# H10R4.net
KiCad netlist of a schematic drawn in EAGLE
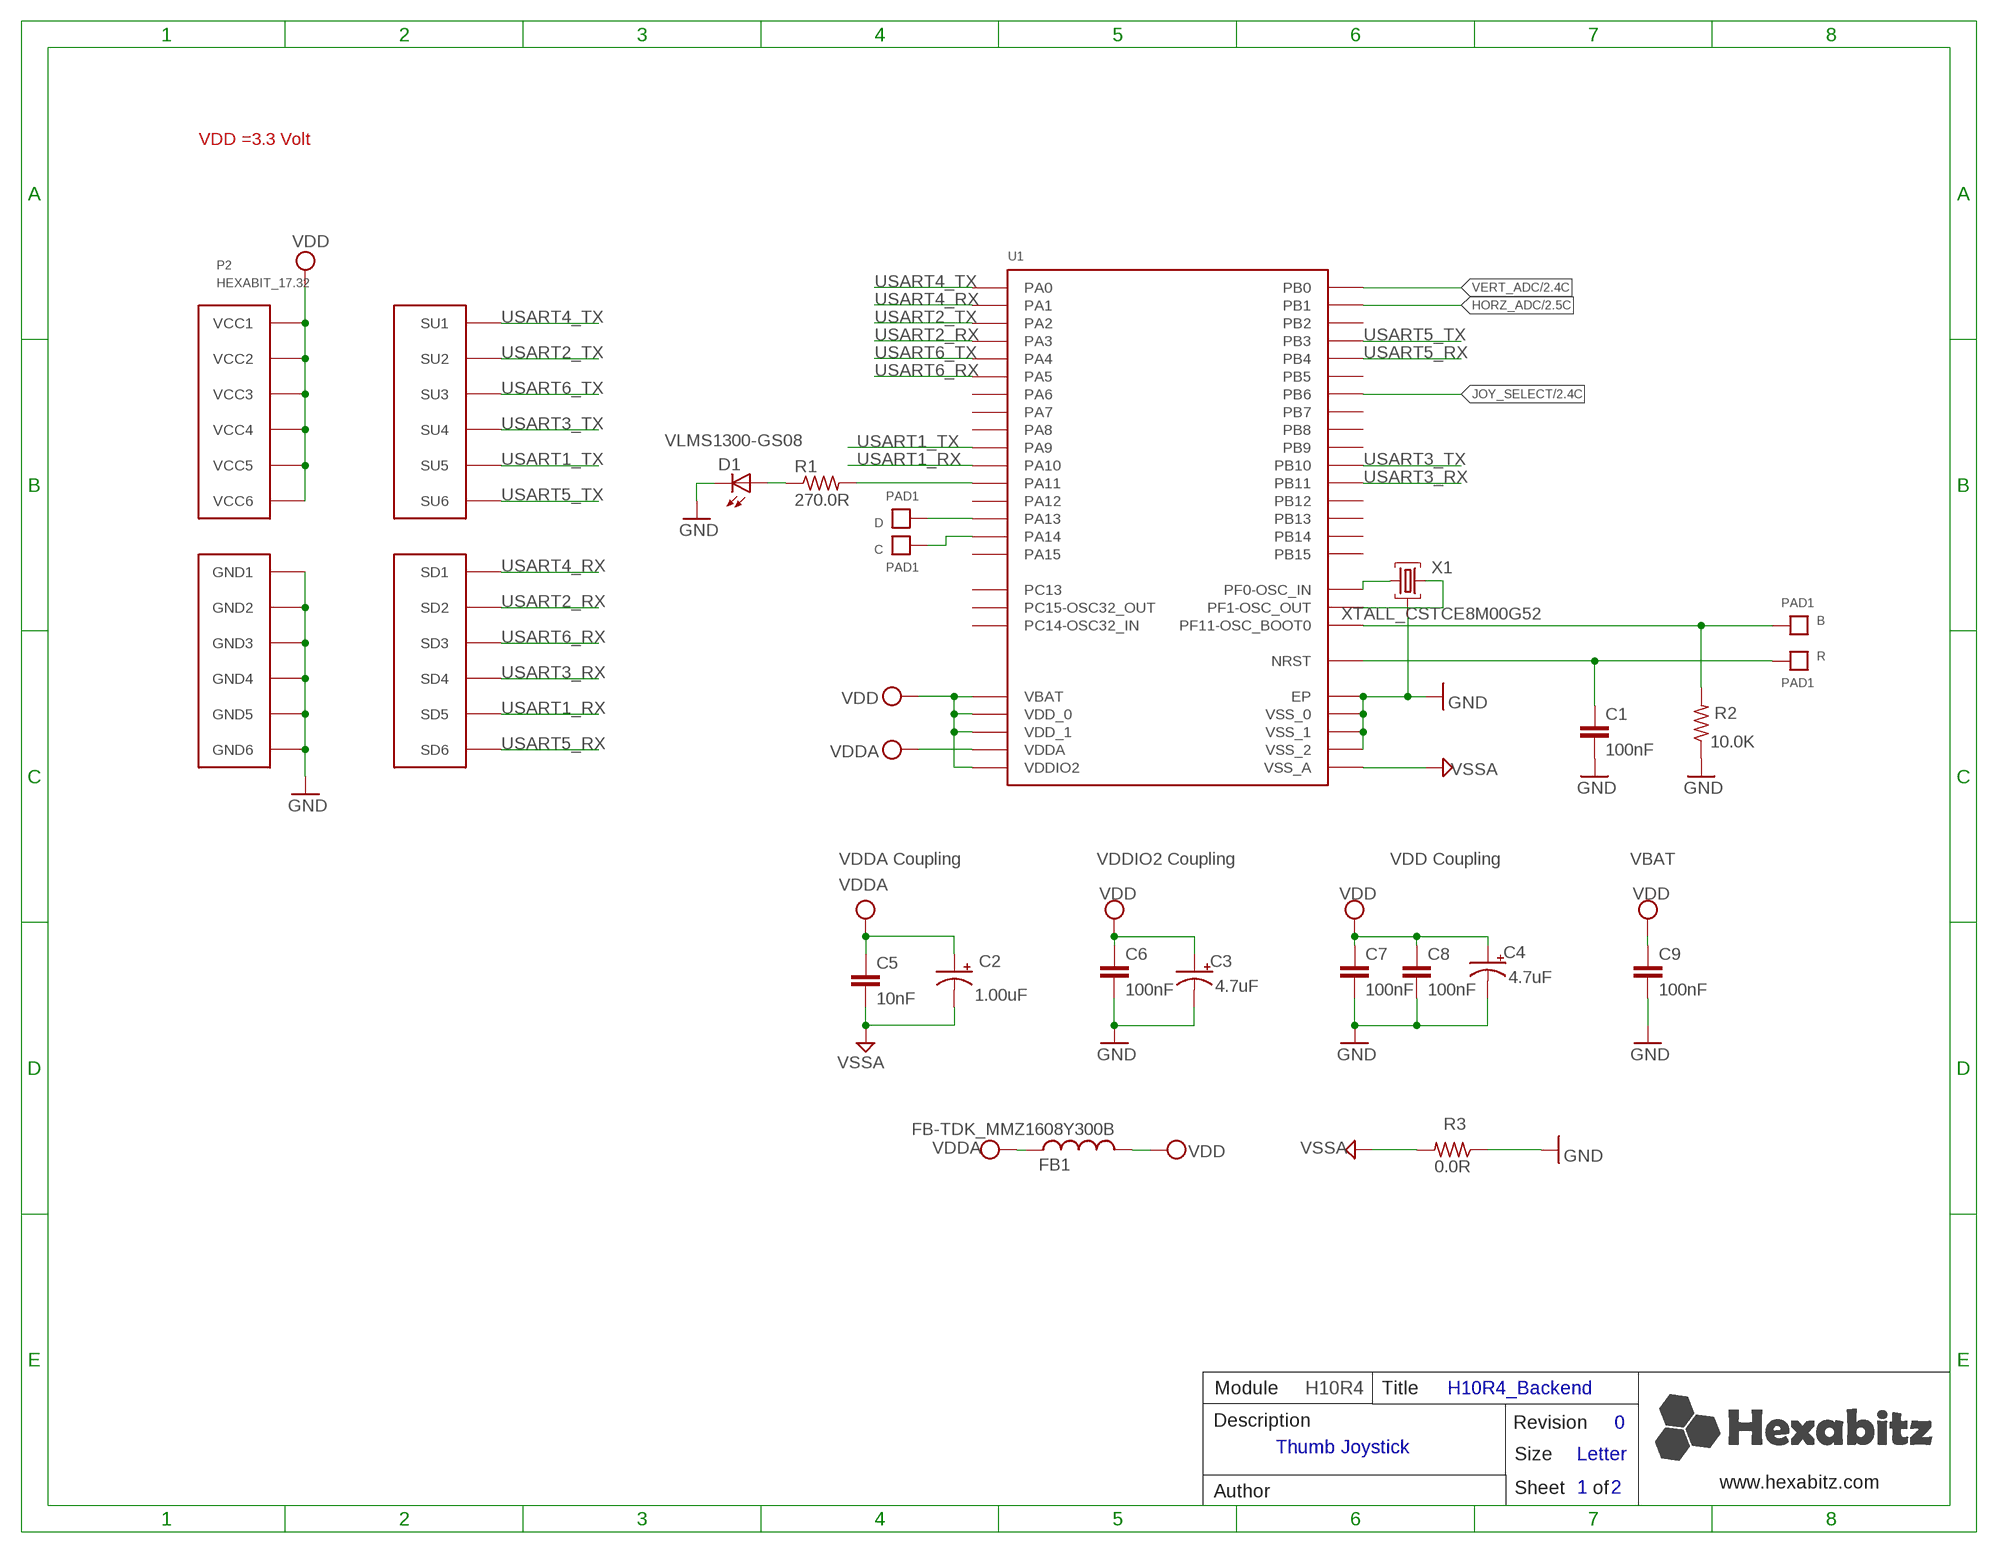
[diagram p0: schematic, sheet 1]
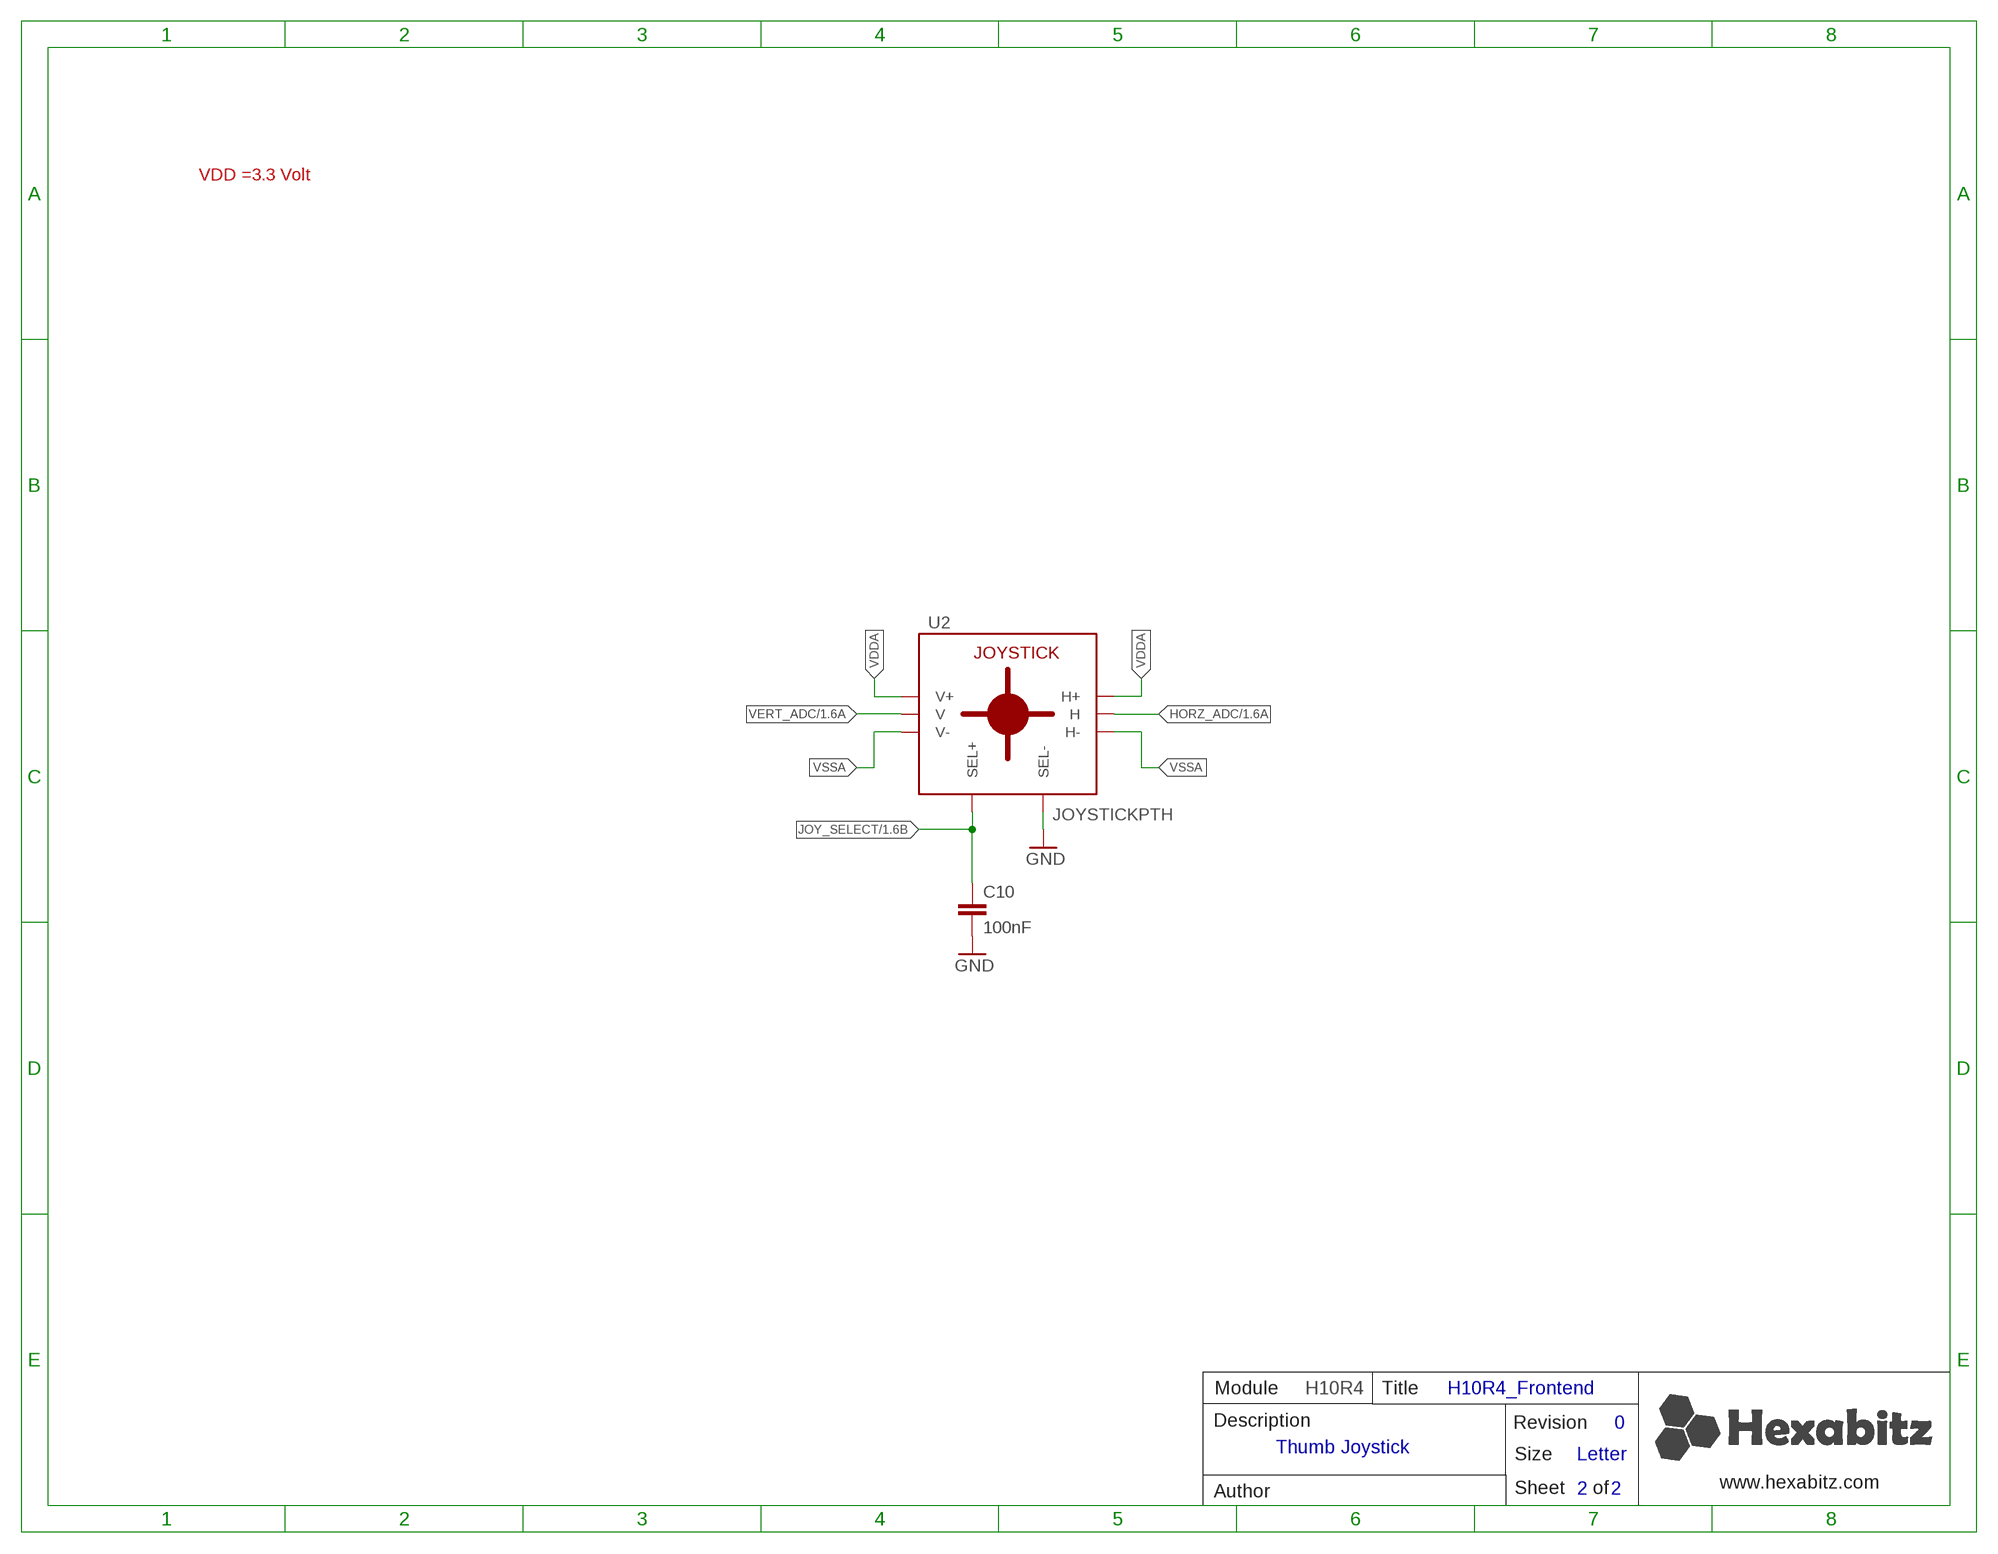
[diagram p1: schematic, sheet 2]

(export (version "E")
  (design (tool "Eeschema 10.0.6"))
  (components
    (comp (ref "B")
      (value "PAD1")
      (footprint "eagle-import:PAD1")
      (libsource (lib "eagle-import") (part "PAD1"))
    )
    (comp (ref "C")
      (value "PAD1")
      (footprint "eagle-import:PAD1")
      (libsource (lib "eagle-import") (part "PAD1"))
    )
    (comp (ref "C1")
      (value "100nF")
      (footprint "eagle-import:C-0603")
      (fields
        (field (name "CAPACITANCE") "100nF")
        (field (name "MFN") "KEMET")
        (field (name "MPN") "C0603C104K8RACTU")
        (field (name "OCTOPART_URL") "https://octopart.com/c0603c104k8ractu-kemet-145075?r=sp&s=9bS9ASSwSEqMCE9KBEQZ0g")
        (field (name "TOLERANCE") "10%")
        (field (name "VOLTAGE_RATING") "10V")
      )
      (libsource (lib "eagle-import") (part "C-0603"))
    )
    (comp (ref "C2")
      (value "1.00uF")
      (footprint "eagle-import:C-0805-POL")
      (fields
        (field (name "CAPACITANCE") "1.00uF")
        (field (name "MFN") "Yageo")
        (field (name "MPN") "CC0805KKX7R7BB105")
        (field (name "OCTOPART_URL") "https://octopart.com/cc0805kkx7r7bb105-yageo-8376555?r=sp&s=YKl1wwtkROau_X5nniH2ig")
        (field (name "TOLERANCE") "10%")
        (field (name "VOLTAGE_RATING") "16V")
      )
      (libsource (lib "eagle-import") (part "C-0805-POL"))
    )
    (comp (ref "C3")
      (value "4.7uF")
      (footprint "eagle-import:C-0805-POL")
      (fields
        (field (name "CAPACITANCE") "4.7uF")
        (field (name "MFN") "Murata")
        (field (name "MPN") "GRM21BC81E475KA12L")
        (field (name "OCTOPART_URL") "https://octopart.com/grm21bc81e475ka12l-murata-10331911?r=sp&s=RY3qZSD8T6mG6TC9CHI5qQ")
        (field (name "TOLERANCE") "10%")
        (field (name "VOLTAGE_RATING") "25V")
      )
      (libsource (lib "eagle-import") (part "C-0805-POL"))
    )
    (comp (ref "C4")
      (value "4.7uF")
      (footprint "eagle-import:C-0805-POL")
      (fields
        (field (name "CAPACITANCE") "4.7uF")
        (field (name "MFN") "Murata")
        (field (name "MPN") "GRM21BC81E475KA12L")
        (field (name "OCTOPART_URL") "https://octopart.com/grm21bc81e475ka12l-murata-10331911?r=sp&s=RY3qZSD8T6mG6TC9CHI5qQ")
        (field (name "TOLERANCE") "10%")
        (field (name "VOLTAGE_RATING") "25V")
      )
      (libsource (lib "eagle-import") (part "C-0805-POL"))
    )
    (comp (ref "C5")
      (value "10nF")
      (footprint "eagle-import:C-0603")
      (fields
        (field (name "CAPACITANCE") "10nF")
        (field (name "MFN") "KEMET")
        (field (name "MPN") "C0603C103K5RACTU")
        (field (name "OCTOPART_URL") "https://octopart.com/c0603c103k5ractu-kemet-133094?r=sp&s=R_iPBxLnSmGqhkU2rIMFpg")
        (field (name "TOLERANCE") "10%")
        (field (name "VOLTAGE_RATING") "50V")
      )
      (libsource (lib "eagle-import") (part "C-0603"))
    )
    (comp (ref "C6")
      (value "100nF")
      (footprint "eagle-import:C-0603")
      (fields
        (field (name "CAPACITANCE") "100nF")
        (field (name "MFN") "KEMET")
        (field (name "MPN") "C0603C104K8RACTU")
        (field (name "OCTOPART_URL") "https://octopart.com/c0603c104k8ractu-kemet-145075?r=sp&s=9bS9ASSwSEqMCE9KBEQZ0g")
        (field (name "TOLERANCE") "10%")
        (field (name "VOLTAGE_RATING") "10V")
      )
      (libsource (lib "eagle-import") (part "C-0603"))
    )
    (comp (ref "C7")
      (value "100nF")
      (footprint "eagle-import:C-0603")
      (fields
        (field (name "CAPACITANCE") "100nF")
        (field (name "MFN") "KEMET")
        (field (name "MPN") "C0603C104K8RACTU")
        (field (name "OCTOPART_URL") "https://octopart.com/c0603c104k8ractu-kemet-145075?r=sp&s=9bS9ASSwSEqMCE9KBEQZ0g")
        (field (name "TOLERANCE") "10%")
        (field (name "VOLTAGE_RATING") "10")
      )
      (libsource (lib "eagle-import") (part "C-0603"))
    )
    (comp (ref "C8")
      (value "100nF")
      (footprint "eagle-import:C-0603")
      (fields
        (field (name "CAPACITANCE") "100nF")
        (field (name "MFN") "KEMET")
        (field (name "MPN") "C0603C104K8RACTU")
        (field (name "OCTOPART_URL") "https://octopart.com/c0603c104k8ractu-kemet-145075?r=sp&s=9bS9ASSwSEqMCE9KBEQZ0g")
        (field (name "TOLERANCE") "10%")
        (field (name "VOLTAGE_RATING") "10V")
      )
      (libsource (lib "eagle-import") (part "C-0603"))
    )
    (comp (ref "C9")
      (value "100nF")
      (footprint "eagle-import:C-0603")
      (fields
        (field (name "CAPACITANCE") "100nF")
        (field (name "MFN") "KEMET")
        (field (name "MPN") "C0603C104K8RACTU")
        (field (name "OCTOPART_URL") "https://octopart.com/c0603c104k8ractu-kemet-145075?r=sp&s=9bS9ASSwSEqMCE9KBEQZ0g")
        (field (name "TOLERANCE") "10V")
        (field (name "VOLTAGE_RATING") "10%")
      )
      (libsource (lib "eagle-import") (part "C-0603"))
    )
    (comp (ref "D")
      (value "PAD1")
      (footprint "eagle-import:PAD1")
      (libsource (lib "eagle-import") (part "PAD1"))
    )
    (comp (ref "D1")
      (value "VLMS1300-GS08")
      (footprint "eagle-import:VLMS1300-GS08")
      (fields
        (field (name "MFN") "Vishay")
        (field (name "MPN") "VLMS1300-GS08")
        (field (name "OCTOPART_URL") "https://octopart.com/vlms1300-gs08-vishay-21709201?r=sp&s=_gcP4_q8T1SC6PJQPTQ9yA")
      )
      (libsource (lib "eagle-import") (part "VLMS1300-GS08"))
    )
    (comp (ref "FB1")
      (value "FB-TDK_MMZ1608Y300B")
      (footprint "eagle-import:FB-TDK_MMZ1608Y300B")
      (fields
        (field (name "MFN") "TDK ")
        (field (name "MPN") "MMZ1608Y300B")
        (field (name "OCTOPART_URL") "https://octopart.com/mmz1608y300b-tdk-368280?r=sp&s=cd9_2ZEqQ9q9UNBuQgHAiA")
      )
      (libsource (lib "eagle-import") (part "FB-TDK_MMZ1608Y300B"))
    )
    (comp (ref "P2")
      (value "HEXABIT_17.32")
      (footprint "eagle-import:HEXABIT_17.32")
      (libsource (lib "eagle-import") (part "HEXABIT_17.32"))
    )
    (comp (ref "R")
      (value "PAD1")
      (footprint "eagle-import:PAD1")
      (libsource (lib "eagle-import") (part "PAD1"))
    )
    (comp (ref "R1")
      (value "270.0R")
      (footprint "eagle-import:R-0603")
      (fields
        (field (name "MFN") "Yageo")
        (field (name "MPN") "RC0603FR-07270RL")
        (field (name "OCTOPART_URL") "https://octopart.com/search?q=RC0603FR-07270RL&start=0")
        (field (name "RESISTANCE") "270.0 Ohm")
        (field (name "TOLERANCE") "1%")
      )
      (libsource (lib "eagle-import") (part "R-0603"))
    )
    (comp (ref "R2")
      (value "10.0K")
      (footprint "eagle-import:R-0603")
      (fields
        (field (name "MFN") "Yageo")
        (field (name "MPN") "RC0603JR-0710KL")
        (field (name "OCTOPART_URL") "https://octopart.com/search?q=RC0603JR-0710KL&start=0")
        (field (name "RESISTANCE") "10.0K Ohm")
        (field (name "TOLERANCE") "5%")
      )
      (libsource (lib "eagle-import") (part "R-0603"))
    )
    (comp (ref "R3")
      (value "0.0R")
      (footprint "eagle-import:R-0603")
      (fields
        (field (name "MFN") "Yageo")
        (field (name "MPN") "RC0603JR-070RL")
        (field (name "OCTOPART_URL") "https://octopart.com/rc0603jr-070rl-yageo-1241539?r=sp&s=X2NteqRjRNWrnx42Y0aliA")
        (field (name "RESISTANCE") "0.0 Ohm")
      )
      (libsource (lib "eagle-import") (part "R-0603"))
    )
    (comp (ref "U1")
      (value "STM32F091CBU6")
      (footprint "eagle-import:STM32F091CBU6")
      (libsource (lib "eagle-import") (part "STM32F091CBU6"))
    )
    (comp (ref "X1")
      (value "XTALL_CSTCE8M00G52")
      (footprint "eagle-import:XTALL_CSTCE8M00G52")
      (fields (field (name "MPN") "CSTCE8M00G52Z-R0"))
      (libsource (lib "eagle-import") (part "XTALL_CSTCE8M00G52"))
    )
    (comp (ref "C10")
      (value "100nF")
      (footprint "eagle-import:C-0603")
      (fields
        (field (name "CAPACITANCE") "100nF")
        (field (name "MFN") "KEMET")
        (field (name "MPN") "C0603C104K8RACTU")
        (field (name "OCTOPART_URL") "https://octopart.com/c0603c104k8ractu-kemet-145075?r=sp&s=9bS9ASSwSEqMCE9KBEQZ0g")
        (field (name "TOLERANCE") "10%")
        (field (name "VOLTAGE_RATING") "10V")
      )
      (libsource (lib "eagle-import") (part "C-0603"))
    )
    (comp (ref "U2")
      (value "JOYSTICKPTH")
      (footprint "eagle-import:JOYSTICK")
      (fields (field (name "MPN") "COM-09032"))
      (libsource (lib "eagle-import") (part "JOYSTICKPTH"))
    )
  )
  (nets
    (net (code "1") (name "GND") (class "Default")
      (node (ref "C1") (pin "2") (pinfunction "2_2") (pintype "passive"))
      (node (ref "C10") (pin "2") (pinfunction "2_2") (pintype "passive"))
      (node (ref "C3") (pin "2") (pinfunction "-_2") (pintype "passive"))
      (node (ref "C4") (pin "2") (pinfunction "-_2") (pintype "passive"))
      (node (ref "C6") (pin "2") (pinfunction "2_2") (pintype "passive"))
      (node (ref "C7") (pin "2") (pinfunction "2_2") (pintype "passive"))
      (node (ref "C8") (pin "2") (pinfunction "2_2") (pintype "passive"))
      (node (ref "C9") (pin "2") (pinfunction "2_2") (pintype "passive"))
      (node (ref "D1") (pin "C") (pinfunction "C_C") (pintype "passive"))
      (node (ref "P2") (pin "10") (pinfunction "GND4_10") (pintype "power_in"))
      (node (ref "P2") (pin "11") (pinfunction "GND5_11") (pintype "power_in"))
      (node (ref "P2") (pin "12") (pinfunction "GND6_12") (pintype "power_in"))
      (node (ref "P2") (pin "7") (pinfunction "GND1_7") (pintype "power_in"))
      (node (ref "P2") (pin "8") (pinfunction "GND2_8") (pintype "power_in"))
      (node (ref "P2") (pin "9") (pinfunction "GND3_9") (pintype "power_in"))
      (node (ref "R2") (pin "1") (pinfunction "1_1") (pintype "passive"))
      (node (ref "R3") (pin "1") (pinfunction "1_1") (pintype "passive"))
      (node (ref "U1") (pin "EP") (pinfunction "EP_EP") (pintype "power_in"))
      (node (ref "U1") (pin "P$23") (pinfunction "VSS_0_P$23") (pintype "power_in"))
      (node (ref "U1") (pin "P$35") (pinfunction "VSS_1_P$35") (pintype "power_in"))
      (node (ref "U1") (pin "P$47") (pinfunction "VSS_2_P$47") (pintype "power_in"))
      (node (ref "U2") (pin "B2A") (pinfunction "SEL-_B2A") (pintype "bidirectional"))
      (node (ref "X1") (pin "P$2") (pinfunction "2_P$2") (pintype "passive"))
    )
    (net (code "2") (name "HORZ_ADC") (class "Default")
      (node (ref "U1") (pin "P$19") (pinfunction "PB1_P$19") (pintype "bidirectional"))
      (node (ref "U2") (pin "H2") (pinfunction "H_H2") (pintype "bidirectional"))
    )
    (net (code "3") (name "JOY_SELECT") (class "Default")
      (node (ref "C10") (pin "1") (pinfunction "1_1") (pintype "passive"))
      (node (ref "U1") (pin "P$42") (pinfunction "PB6_P$42") (pintype "bidirectional"))
      (node (ref "U2") (pin "B1A") (pinfunction "SEL+_B1A") (pintype "bidirectional"))
    )
    (net (code "4") (name "Net-(D1-PadA)") (class "Default")
      (node (ref "D1") (pin "A") (pinfunction "A_A") (pintype "passive"))
      (node (ref "R1") (pin "1") (pinfunction "1_1") (pintype "passive"))
    )
    (net (code "5") (name "Net-(U1-NRST)") (class "Default")
      (node (ref "C1") (pin "1") (pinfunction "1_1") (pintype "passive"))
      (node (ref "R") (pin "P$1") (pinfunction "P$1_P$1") (pintype "passive"))
      (node (ref "R") (pin "P$2") (pinfunction "P$1_P$2") (pintype "passive"))
      (node (ref "U1") (pin "P$7") (pinfunction "NRST_P$7") (pintype "passive"))
    )
    (net (code "6") (name "Net-(U1-PA11)") (class "Default")
      (node (ref "R1") (pin "2") (pinfunction "2_2") (pintype "passive"))
      (node (ref "U1") (pin "P$32") (pinfunction "PA11_P$32") (pintype "bidirectional"))
    )
    (net (code "7") (name "Net-(U1-PA13)") (class "Default")
      (node (ref "D") (pin "P$1") (pinfunction "P$1_P$1") (pintype "passive"))
      (node (ref "D") (pin "P$2") (pinfunction "P$1_P$2") (pintype "passive"))
      (node (ref "U1") (pin "P$34") (pinfunction "PA13_P$34") (pintype "bidirectional"))
    )
    (net (code "8") (name "Net-(U1-PA14)") (class "Default")
      (node (ref "C") (pin "P$1") (pinfunction "P$1_P$1") (pintype "passive"))
      (node (ref "C") (pin "P$2") (pinfunction "P$1_P$2") (pintype "passive"))
      (node (ref "U1") (pin "P$37") (pinfunction "PA14_P$37") (pintype "bidirectional"))
    )
    (net (code "9") (name "Net-(U1-PF0-OSC_IN)") (class "Default")
      (node (ref "U1") (pin "P$5") (pinfunction "PF0-OSC_IN_P$5") (pintype "bidirectional"))
      (node (ref "X1") (pin "P$1") (pinfunction "1_P$1") (pintype "passive"))
    )
    (net (code "10") (name "Net-(U1-PF1-OSC_OUT)") (class "Default")
      (node (ref "U1") (pin "P$6") (pinfunction "PF1-OSC_OUT_P$6") (pintype "bidirectional"))
      (node (ref "X1") (pin "P$3") (pinfunction "3_P$3") (pintype "passive"))
    )
    (net (code "11") (name "Net-(U1-PF11-OSC_BOOT0)") (class "Default")
      (node (ref "B") (pin "P$1") (pinfunction "P$1_P$1") (pintype "passive"))
      (node (ref "B") (pin "P$2") (pinfunction "P$1_P$2") (pintype "passive"))
      (node (ref "R2") (pin "2") (pinfunction "2_2") (pintype "passive"))
      (node (ref "U1") (pin "P$44") (pinfunction "PF11-OSC_BOOT0_P$44") (pintype "bidirectional"))
    )
    (net (code "12") (name "USART1_RX") (class "Default")
      (node (ref "P2") (pin "23") (pinfunction "SD5_23") (pintype "bidirectional"))
      (node (ref "U1") (pin "P$31") (pinfunction "PA10_P$31") (pintype "bidirectional"))
    )
    (net (code "13") (name "USART1_TX") (class "Default")
      (node (ref "P2") (pin "17") (pinfunction "SU5_17") (pintype "bidirectional"))
      (node (ref "U1") (pin "P$30") (pinfunction "PA9_P$30") (pintype "bidirectional"))
    )
    (net (code "14") (name "USART2_RX") (class "Default")
      (node (ref "P2") (pin "20") (pinfunction "SD2_20") (pintype "bidirectional"))
      (node (ref "U1") (pin "P$13") (pinfunction "PA3_P$13") (pintype "bidirectional"))
    )
    (net (code "15") (name "USART2_TX") (class "Default")
      (node (ref "P2") (pin "14") (pinfunction "SU2_14") (pintype "bidirectional"))
      (node (ref "U1") (pin "P$12") (pinfunction "PA2_P$12") (pintype "bidirectional"))
    )
    (net (code "16") (name "USART3_RX") (class "Default")
      (node (ref "P2") (pin "22") (pinfunction "SD4_22") (pintype "bidirectional"))
      (node (ref "U1") (pin "P$22") (pinfunction "PB11_P$22") (pintype "bidirectional"))
    )
    (net (code "17") (name "USART3_TX") (class "Default")
      (node (ref "P2") (pin "16") (pinfunction "SU4_16") (pintype "bidirectional"))
      (node (ref "U1") (pin "P$21") (pinfunction "PB10_P$21") (pintype "bidirectional"))
    )
    (net (code "18") (name "USART4_RX") (class "Default")
      (node (ref "P2") (pin "19") (pinfunction "SD1_19") (pintype "bidirectional"))
      (node (ref "U1") (pin "P$11") (pinfunction "PA1_P$11") (pintype "bidirectional"))
    )
    (net (code "19") (name "USART4_TX") (class "Default")
      (node (ref "P2") (pin "13") (pinfunction "SU1_13") (pintype "bidirectional"))
      (node (ref "U1") (pin "P$10") (pinfunction "PA0_P$10") (pintype "bidirectional"))
    )
    (net (code "20") (name "USART5_RX") (class "Default")
      (node (ref "P2") (pin "25") (pinfunction "SD6_25") (pintype "bidirectional"))
      (node (ref "U1") (pin "P$40") (pinfunction "PB4_P$40") (pintype "bidirectional"))
    )
    (net (code "21") (name "USART5_TX") (class "Default")
      (node (ref "P2") (pin "18") (pinfunction "SU6_18") (pintype "bidirectional"))
      (node (ref "U1") (pin "P$39") (pinfunction "PB3_P$39") (pintype "bidirectional"))
    )
    (net (code "22") (name "USART6_RX") (class "Default")
      (node (ref "P2") (pin "21") (pinfunction "SD3_21") (pintype "bidirectional"))
      (node (ref "U1") (pin "P$15") (pinfunction "PA5_P$15") (pintype "bidirectional"))
    )
    (net (code "23") (name "USART6_TX") (class "Default")
      (node (ref "P2") (pin "15") (pinfunction "SU3_15") (pintype "bidirectional"))
      (node (ref "U1") (pin "P$14") (pinfunction "PA4_P$14") (pintype "bidirectional"))
    )
    (net (code "24") (name "VDD") (class "Default")
      (node (ref "C3") (pin "1") (pinfunction "+_1") (pintype "passive"))
      (node (ref "C4") (pin "1") (pinfunction "+_1") (pintype "passive"))
      (node (ref "C6") (pin "1") (pinfunction "1_1") (pintype "passive"))
      (node (ref "C7") (pin "1") (pinfunction "1_1") (pintype "passive"))
      (node (ref "C8") (pin "1") (pinfunction "1_1") (pintype "passive"))
      (node (ref "C9") (pin "1") (pinfunction "1_1") (pintype "passive"))
      (node (ref "FB1") (pin "2") (pinfunction "2_2") (pintype "passive"))
      (node (ref "P2") (pin "1") (pinfunction "VCC1_1") (pintype "power_in"))
      (node (ref "P2") (pin "2") (pinfunction "VCC2_2") (pintype "power_in"))
      (node (ref "P2") (pin "3") (pinfunction "VCC3_3") (pintype "power_in"))
      (node (ref "P2") (pin "4") (pinfunction "VCC4_4") (pintype "power_in"))
      (node (ref "P2") (pin "5") (pinfunction "VCC5_5") (pintype "power_in"))
      (node (ref "P2") (pin "6") (pinfunction "VCC6_6") (pintype "power_in"))
      (node (ref "U1") (pin "P$1") (pinfunction "VBAT_P$1") (pintype "power_in"))
      (node (ref "U1") (pin "P$24") (pinfunction "VDD_0_P$24") (pintype "power_in"))
      (node (ref "U1") (pin "P$36") (pinfunction "VDDIO2_P$36") (pintype "power_in"))
      (node (ref "U1") (pin "P$48") (pinfunction "VDD_1_P$48") (pintype "power_in"))
    )
    (net (code "25") (name "VDDA") (class "Default")
      (node (ref "C2") (pin "1") (pinfunction "+_1") (pintype "passive"))
      (node (ref "C5") (pin "1") (pinfunction "1_1") (pintype "passive"))
      (node (ref "FB1") (pin "1") (pinfunction "1_1") (pintype "passive"))
      (node (ref "U1") (pin "P$9") (pinfunction "VDDA_P$9") (pintype "power_in"))
      (node (ref "U2") (pin "H1") (pinfunction "H+_H1") (pintype "bidirectional"))
      (node (ref "U2") (pin "V1") (pinfunction "V+_V1") (pintype "bidirectional"))
    )
    (net (code "26") (name "VERT_ADC") (class "Default")
      (node (ref "U1") (pin "P$18") (pinfunction "PB0_P$18") (pintype "bidirectional"))
      (node (ref "U2") (pin "V2") (pinfunction "V_V2") (pintype "bidirectional"))
    )
    (net (code "27") (name "VSSA") (class "Default")
      (node (ref "C2") (pin "2") (pinfunction "-_2") (pintype "passive"))
      (node (ref "C5") (pin "2") (pinfunction "2_2") (pintype "passive"))
      (node (ref "R3") (pin "2") (pinfunction "2_2") (pintype "passive"))
      (node (ref "U1") (pin "P$8") (pinfunction "VSS_A_P$8") (pintype "power_in"))
      (node (ref "U2") (pin "H3") (pinfunction "H-_H3") (pintype "bidirectional"))
      (node (ref "U2") (pin "V3") (pinfunction "V-_V3") (pintype "bidirectional"))
    )
    (net (code "28") (name "unconnected-(U1-PA6-PadP$16)") (class "Default")
      (node (ref "U1") (pin "P$16") (pinfunction "PA6_P$16") (pintype "bidirectional"))
    )
    (net (code "29") (name "unconnected-(U1-PA7-PadP$17)") (class "Default")
      (node (ref "U1") (pin "P$17") (pinfunction "PA7_P$17") (pintype "bidirectional"))
    )
    (net (code "30") (name "unconnected-(U1-PA8-PadP$29)") (class "Default")
      (node (ref "U1") (pin "P$29") (pinfunction "PA8_P$29") (pintype "bidirectional"))
    )
    (net (code "31") (name "unconnected-(U1-PA12-PadP$33)") (class "Default")
      (node (ref "U1") (pin "P$33") (pinfunction "PA12_P$33") (pintype "bidirectional"))
    )
    (net (code "32") (name "unconnected-(U1-PA15-PadP$38)") (class "Default")
      (node (ref "U1") (pin "P$38") (pinfunction "PA15_P$38") (pintype "bidirectional"))
    )
    (net (code "33") (name "unconnected-(U1-PB2-PadP$20)") (class "Default")
      (node (ref "U1") (pin "P$20") (pinfunction "PB2_P$20") (pintype "bidirectional"))
    )
    (net (code "34") (name "unconnected-(U1-PB5-PadP$41)") (class "Default")
      (node (ref "U1") (pin "P$41") (pinfunction "PB5_P$41") (pintype "bidirectional"))
    )
    (net (code "35") (name "unconnected-(U1-PB7-PadP$43)") (class "Default")
      (node (ref "U1") (pin "P$43") (pinfunction "PB7_P$43") (pintype "bidirectional"))
    )
    (net (code "36") (name "unconnected-(U1-PB8-PadP$45)") (class "Default")
      (node (ref "U1") (pin "P$45") (pinfunction "PB8_P$45") (pintype "bidirectional"))
    )
    (net (code "37") (name "unconnected-(U1-PB9-PadP$46)") (class "Default")
      (node (ref "U1") (pin "P$46") (pinfunction "PB9_P$46") (pintype "bidirectional"))
    )
    (net (code "38") (name "unconnected-(U1-PB12-PadP$25)") (class "Default")
      (node (ref "U1") (pin "P$25") (pinfunction "PB12_P$25") (pintype "bidirectional"))
    )
    (net (code "39") (name "unconnected-(U1-PB13-PadP$26)") (class "Default")
      (node (ref "U1") (pin "P$26") (pinfunction "PB13_P$26") (pintype "bidirectional"))
    )
    (net (code "40") (name "unconnected-(U1-PB14-PadP$27)") (class "Default")
      (node (ref "U1") (pin "P$27") (pinfunction "PB14_P$27") (pintype "bidirectional"))
    )
    (net (code "41") (name "unconnected-(U1-PB15-PadP$28)") (class "Default")
      (node (ref "U1") (pin "P$28") (pinfunction "PB15_P$28") (pintype "bidirectional"))
    )
    (net (code "42") (name "unconnected-(U1-PC13-PadP$2)") (class "Default")
      (node (ref "U1") (pin "P$2") (pinfunction "PC13_P$2") (pintype "bidirectional"))
    )
    (net (code "43") (name "unconnected-(U1-PC14-OSC32_IN-PadP$3)") (class "Default")
      (node (ref "U1") (pin "P$3") (pinfunction "PC14-OSC32_IN_P$3") (pintype "bidirectional"))
    )
    (net (code "44") (name "unconnected-(U1-PC15-OSC32_OUT-PadP$4)") (class "Default")
      (node (ref "U1") (pin "P$4") (pinfunction "PC15-OSC32_OUT_P$4") (pintype "bidirectional"))
    )
  )
)
